# SCROD_CONN_A2.net
KiCad netlist of a schematic drawn in Altium Designer
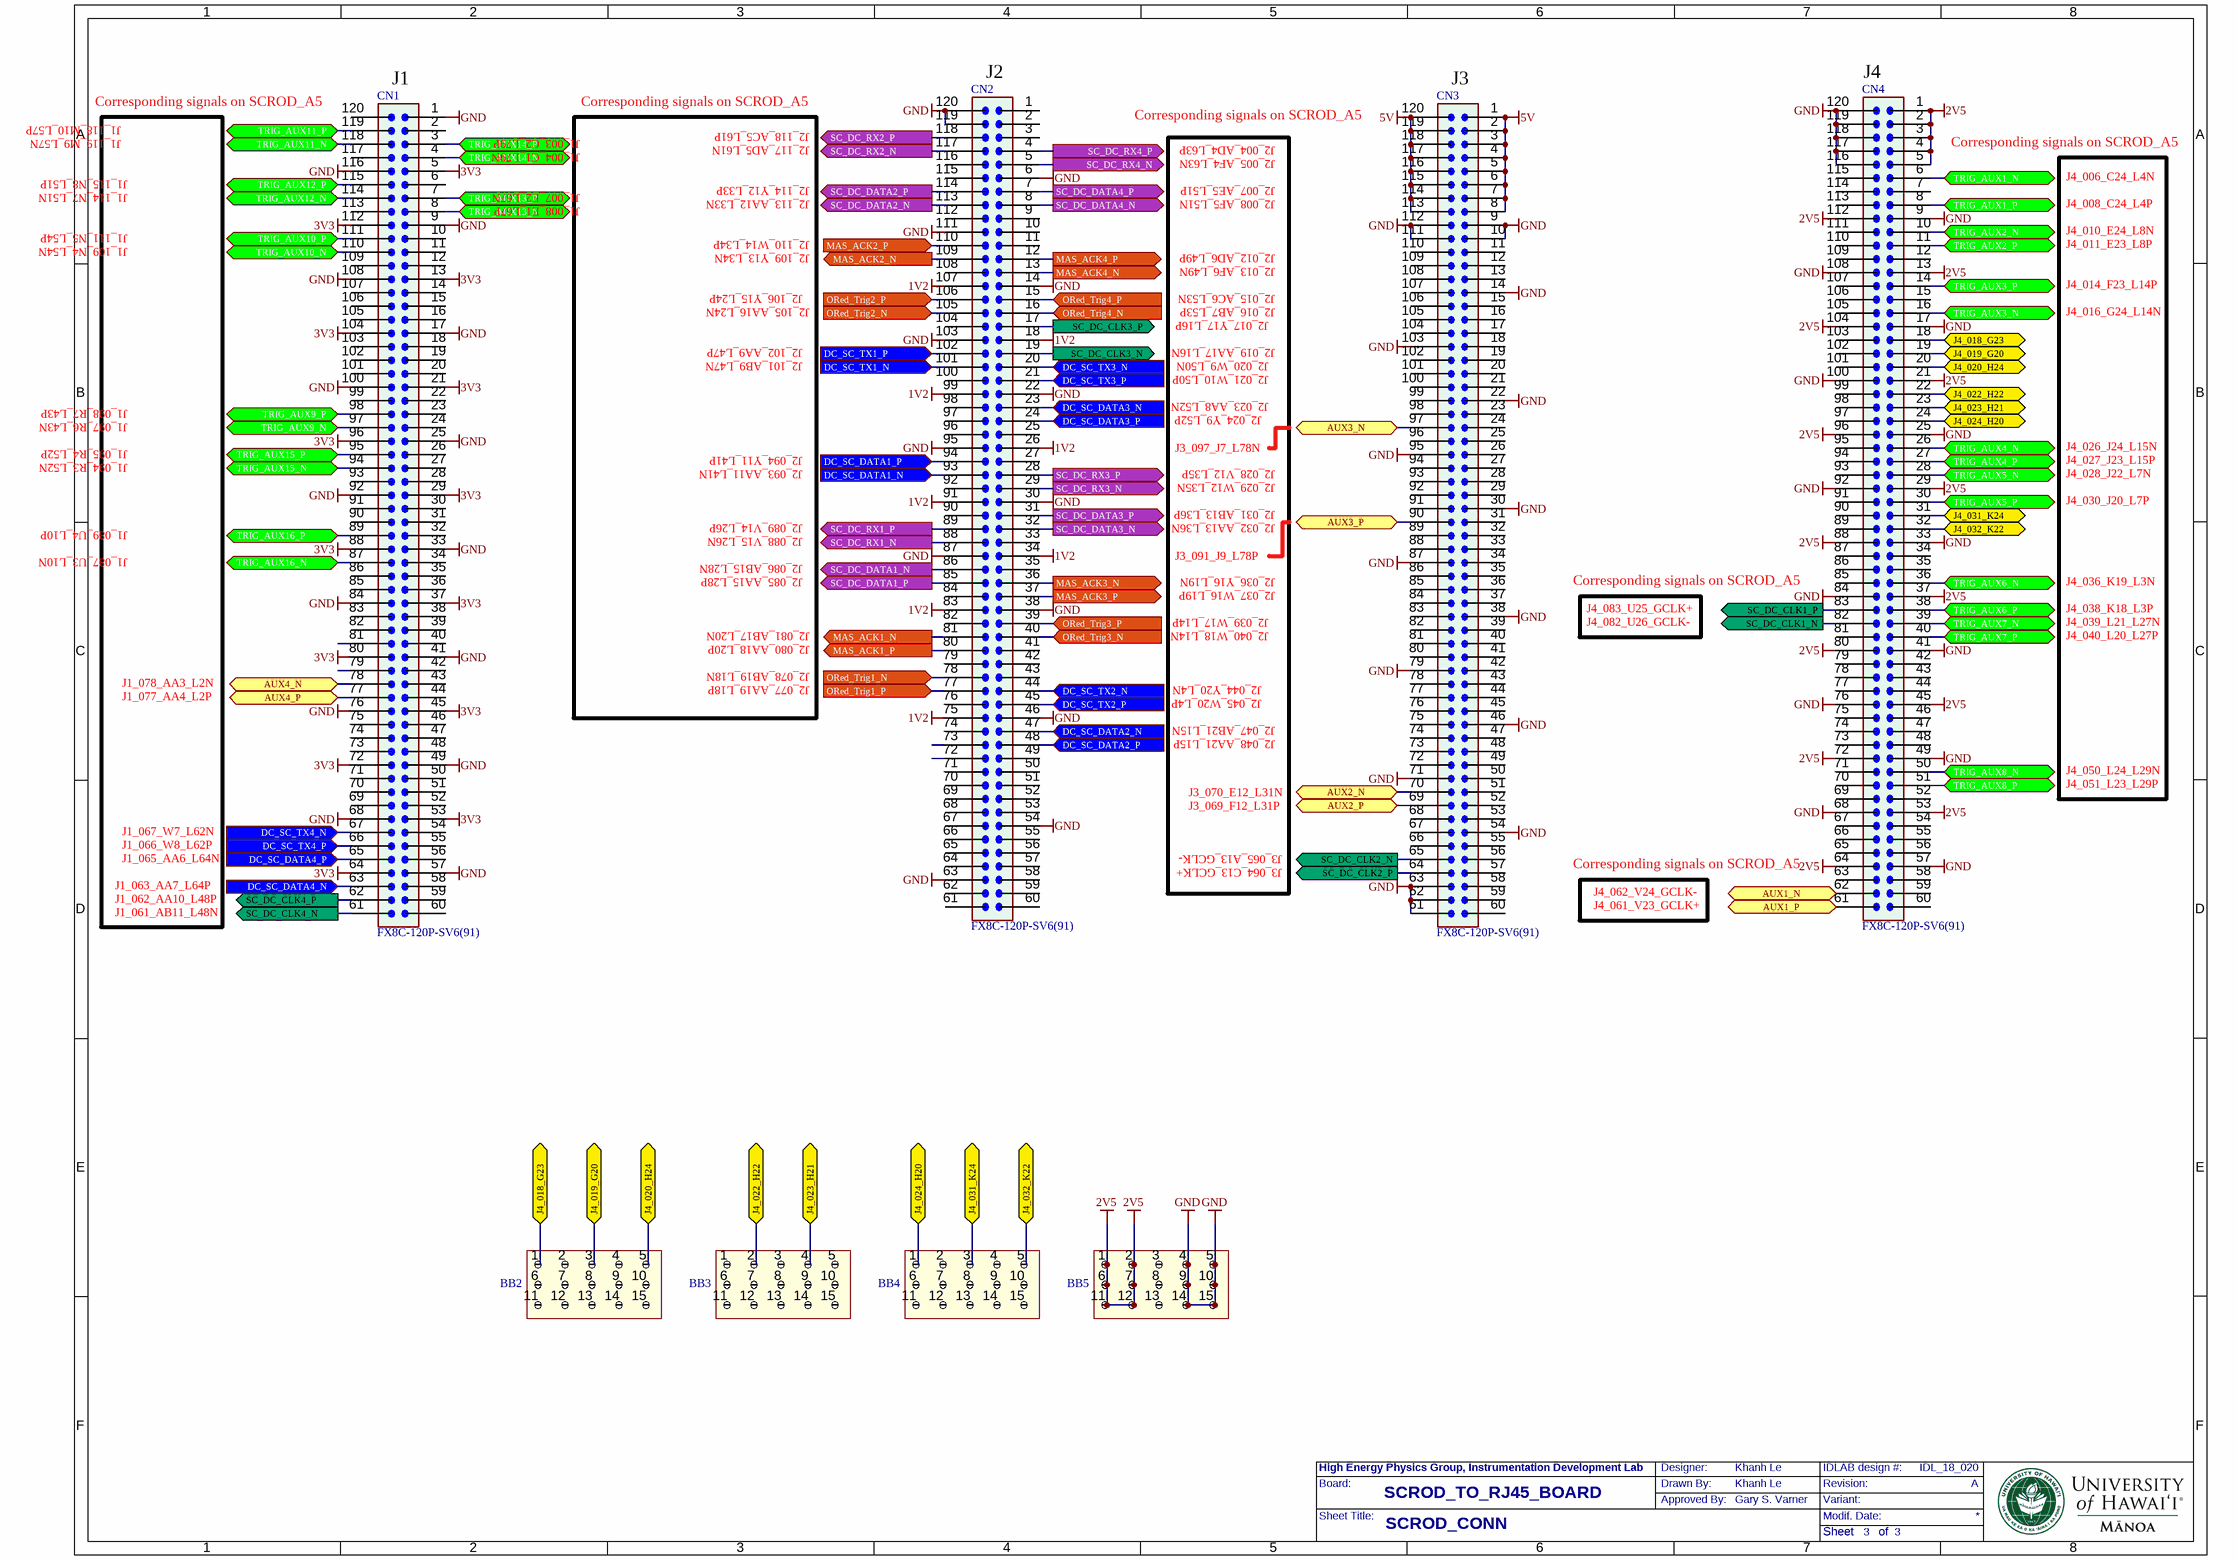
[diagram p0: SCROD_CONN_A2.SchDoc]

(export (version "E")
  (design (tool "Eeschema 10.0.6"))
  (components
    (comp (ref "BB2")
      (value "~")
      (footprint "Breadboard_3x5_100mil_pitch")
      (description "3X5 100mil pitch Breadboard")
      (libsource (lib "BMD") (part "3X5 Breadboard"))
    )
    (comp (ref "BB3")
      (value "~")
      (footprint "Breadboard_3x5_100mil_pitch")
      (description "3X5 100mil pitch Breadboard")
      (libsource (lib "BMD") (part "3X5 Breadboard"))
    )
    (comp (ref "BB4")
      (value "~")
      (footprint "Breadboard_3x5_100mil_pitch")
      (description "3X5 100mil pitch Breadboard")
      (libsource (lib "BMD") (part "3X5 Breadboard"))
    )
    (comp (ref "BB5")
      (value "~")
      (footprint "Breadboard_3x5_100mil_pitch")
      (description "3X5 100mil pitch Breadboard")
      (libsource (lib "BMD") (part "3X5 Breadboard"))
    )
    (comp (ref "CN1")
      (value "FX8C-120P-SV6(91)")
      (footprint "FX8C-120P-SV6(91)")
      (description "Hirose Connector 120pin SMD R0.6mm male")
      (fields (field (name "MANUFACTURER") "Hirose"))
      (libsource (lib "IDlab") (part "CN_FX8C-120P-SV6(91)"))
    )
    (comp (ref "CN2")
      (value "FX8C-120P-SV6(91)")
      (footprint "FX8C-120P-SV6(91)")
      (description "Hirose Connector 120pin SMD R0.6mm male")
      (fields (field (name "MANUFACTURER") "Hirose"))
      (libsource (lib "IDlab") (part "CN_FX8C-120P-SV6(91)"))
    )
    (comp (ref "CN3")
      (value "FX8C-120P-SV6(91)")
      (footprint "FX8C-120P-SV6(91)")
      (description "Hirose Connector 120pin SMD R0.6mm male")
      (fields (field (name "MANUFACTURER") "Hirose"))
      (libsource (lib "IDlab") (part "CN_FX8C-120P-SV6(91)"))
    )
    (comp (ref "CN4")
      (value "FX8C-120P-SV6(91)")
      (footprint "FX8C-120P-SV6(91)")
      (description "Hirose Connector 120pin SMD R0.6mm male")
      (fields (field (name "MANUFACTURER") "Hirose"))
      (libsource (lib "IDlab") (part "CN_FX8C-120P-SV6(91)"))
    )
  )
  (nets
    (net (code "1") (name "/AUX1_N") (class "Default") (node (ref "CN4") (pin "62") (pintype "passive")))
    (net (code "2") (name "/AUX1_P") (class "Default") (node (ref "CN4") (pin "61") (pintype "passive")))
    (net (code "3") (name "/AUX2_N") (class "Default") (node (ref "CN3") (pin "70") (pintype "passive")))
    (net (code "4") (name "/AUX2_P") (class "Default") (node (ref "CN3") (pin "69") (pintype "passive")))
    (net (code "5") (name "/AUX3_N") (class "Default") (node (ref "CN3") (pin "97") (pintype "passive")))
    (net (code "6") (name "/AUX3_P") (class "Default") (node (ref "CN3") (pin "90") (pintype "passive")))
    (net (code "7") (name "/AUX4_N") (class "Default") (node (ref "CN1") (pin "78") (pintype "passive")))
    (net (code "8") (name "/AUX4_P") (class "Default") (node (ref "CN1") (pin "77") (pintype "passive")))
    (net (code "9") (name "/DC_SC_DATA1_N") (class "Default")
      (node (ref "CN2") (pin "93") (pintype "passive"))
    )
    (net (code "10") (name "/DC_SC_DATA1_P") (class "Default")
      (node (ref "CN2") (pin "94") (pintype "passive"))
    )
    (net (code "11") (name "/DC_SC_DATA2_N") (class "Default")
      (node (ref "CN2") (pin "47") (pintype "passive"))
    )
    (net (code "12") (name "/DC_SC_DATA2_P") (class "Default")
      (node (ref "CN2") (pin "48") (pintype "passive"))
    )
    (net (code "13") (name "/DC_SC_DATA3_N") (class "Default")
      (node (ref "CN2") (pin "23") (pintype "passive"))
    )
    (net (code "14") (name "/DC_SC_DATA3_P") (class "Default")
      (node (ref "CN2") (pin "24") (pintype "passive"))
    )
    (net (code "15") (name "/DC_SC_DATA4_N") (class "Default")
      (node (ref "CN1") (pin "63") (pintype "passive"))
    )
    (net (code "16") (name "/DC_SC_DATA4_P") (class "Default")
      (node (ref "CN1") (pin "65") (pintype "passive"))
    )
    (net (code "17") (name "/DC_SC_TX1_N") (class "Default")
      (node (ref "CN2") (pin "101") (pintype "passive"))
    )
    (net (code "18") (name "/DC_SC_TX1_P") (class "Default")
      (node (ref "CN2") (pin "102") (pintype "passive"))
    )
    (net (code "19") (name "/DC_SC_TX2_N") (class "Default")
      (node (ref "CN2") (pin "44") (pintype "passive"))
    )
    (net (code "20") (name "/DC_SC_TX2_P") (class "Default")
      (node (ref "CN2") (pin "45") (pintype "passive"))
    )
    (net (code "21") (name "/DC_SC_TX3_N") (class "Default")
      (node (ref "CN2") (pin "20") (pintype "passive"))
    )
    (net (code "22") (name "/DC_SC_TX3_P") (class "Default")
      (node (ref "CN2") (pin "21") (pintype "passive"))
    )
    (net (code "23") (name "/DC_SC_TX4_N") (class "Default")
      (node (ref "CN1") (pin "67") (pintype "passive"))
    )
    (net (code "24") (name "/DC_SC_TX4_P") (class "Default")
      (node (ref "CN1") (pin "66") (pintype "passive"))
    )
    (net (code "25") (name "/J4_018_G23") (class "Default")
      (node (ref "BB2") (pin "1") (pinfunction "1_1") (pintype "passive"))
      (node (ref "CN4") (pin "18") (pintype "passive"))
    )
    (net (code "26") (name "/J4_019_G20") (class "Default")
      (node (ref "BB2") (pin "3") (pinfunction "3_3") (pintype "passive"))
      (node (ref "CN4") (pin "19") (pintype "passive"))
    )
    (net (code "27") (name "/J4_020_H24") (class "Default")
      (node (ref "BB2") (pin "5") (pinfunction "5_5") (pintype "passive"))
      (node (ref "CN4") (pin "20") (pintype "passive"))
    )
    (net (code "28") (name "/J4_022_H22") (class "Default")
      (node (ref "BB3") (pin "2") (pinfunction "2_2") (pintype "passive"))
      (node (ref "CN4") (pin "22") (pintype "passive"))
    )
    (net (code "29") (name "/J4_023_H21") (class "Default")
      (node (ref "BB3") (pin "4") (pinfunction "4_4") (pintype "passive"))
      (node (ref "CN4") (pin "23") (pintype "passive"))
    )
    (net (code "30") (name "/J4_024_H20") (class "Default")
      (node (ref "BB4") (pin "1") (pinfunction "1_1") (pintype "passive"))
      (node (ref "CN4") (pin "24") (pintype "passive"))
    )
    (net (code "31") (name "/J4_031_K24") (class "Default")
      (node (ref "BB4") (pin "3") (pinfunction "3_3") (pintype "passive"))
      (node (ref "CN4") (pin "31") (pintype "passive"))
    )
    (net (code "32") (name "/J4_032_K22") (class "Default")
      (node (ref "BB4") (pin "5") (pinfunction "5_5") (pintype "passive"))
      (node (ref "CN4") (pin "32") (pintype "passive"))
    )
    (net (code "33") (name "/MAS_ACK1_N") (class "Default") (node (ref "CN2") (pin "81") (pintype "passive")))
    (net (code "34") (name "/MAS_ACK1_P") (class "Default") (node (ref "CN2") (pin "80") (pintype "passive")))
    (net (code "35") (name "/MAS_ACK2_N") (class "Default")
      (node (ref "CN2") (pin "109") (pintype "passive"))
    )
    (net (code "36") (name "/MAS_ACK2_P") (class "Default")
      (node (ref "CN2") (pin "110") (pintype "passive"))
    )
    (net (code "37") (name "/MAS_ACK3_N") (class "Default") (node (ref "CN2") (pin "36") (pintype "passive")))
    (net (code "38") (name "/MAS_ACK3_P") (class "Default") (node (ref "CN2") (pin "37") (pintype "passive")))
    (net (code "39") (name "/MAS_ACK4_N") (class "Default") (node (ref "CN2") (pin "13") (pintype "passive")))
    (net (code "40") (name "/MAS_ACK4_P") (class "Default") (node (ref "CN2") (pin "12") (pintype "passive")))
    (net (code "41") (name "/ORed_Trig1_N") (class "Default")
      (node (ref "CN2") (pin "78") (pintype "passive"))
    )
    (net (code "42") (name "/ORed_Trig1_P") (class "Default")
      (node (ref "CN2") (pin "77") (pintype "passive"))
    )
    (net (code "43") (name "/ORed_Trig2_N") (class "Default")
      (node (ref "CN2") (pin "105") (pintype "passive"))
    )
    (net (code "44") (name "/ORed_Trig2_P") (class "Default")
      (node (ref "CN2") (pin "106") (pintype "passive"))
    )
    (net (code "45") (name "/ORed_Trig3_N") (class "Default")
      (node (ref "CN2") (pin "40") (pintype "passive"))
    )
    (net (code "46") (name "/ORed_Trig3_P") (class "Default")
      (node (ref "CN2") (pin "39") (pintype "passive"))
    )
    (net (code "47") (name "/ORed_Trig4_N") (class "Default")
      (node (ref "CN2") (pin "16") (pintype "passive"))
    )
    (net (code "48") (name "/ORed_Trig4_P") (class "Default")
      (node (ref "CN2") (pin "15") (pintype "passive"))
    )
    (net (code "49") (name "/SC_DC_CLK1_N") (class "Default")
      (node (ref "CN4") (pin "82") (pintype "passive"))
    )
    (net (code "50") (name "/SC_DC_CLK1_P") (class "Default")
      (node (ref "CN4") (pin "83") (pintype "passive"))
    )
    (net (code "51") (name "/SC_DC_CLK2_N") (class "Default")
      (node (ref "CN3") (pin "65") (pintype "passive"))
    )
    (net (code "52") (name "/SC_DC_CLK2_P") (class "Default")
      (node (ref "CN3") (pin "64") (pintype "passive"))
    )
    (net (code "53") (name "/SC_DC_CLK3_N") (class "Default")
      (node (ref "CN2") (pin "19") (pintype "passive"))
    )
    (net (code "54") (name "/SC_DC_CLK3_P") (class "Default")
      (node (ref "CN2") (pin "17") (pintype "passive"))
    )
    (net (code "55") (name "/SC_DC_CLK4_N") (class "Default")
      (node (ref "CN1") (pin "61") (pintype "passive"))
    )
    (net (code "56") (name "/SC_DC_CLK4_P") (class "Default")
      (node (ref "CN1") (pin "62") (pintype "passive"))
    )
    (net (code "57") (name "/SC_DC_DATA1_N") (class "Default")
      (node (ref "CN2") (pin "86") (pintype "passive"))
    )
    (net (code "58") (name "/SC_DC_DATA1_P") (class "Default")
      (node (ref "CN2") (pin "85") (pintype "passive"))
    )
    (net (code "59") (name "/SC_DC_DATA2_N") (class "Default")
      (node (ref "CN2") (pin "113") (pintype "passive"))
    )
    (net (code "60") (name "/SC_DC_DATA2_P") (class "Default")
      (node (ref "CN2") (pin "114") (pintype "passive"))
    )
    (net (code "61") (name "/SC_DC_DATA3_N") (class "Default")
      (node (ref "CN2") (pin "32") (pintype "passive"))
    )
    (net (code "62") (name "/SC_DC_DATA3_P") (class "Default")
      (node (ref "CN2") (pin "31") (pintype "passive"))
    )
    (net (code "63") (name "/SC_DC_DATA4_N") (class "Default")
      (node (ref "CN2") (pin "8") (pintype "passive"))
    )
    (net (code "64") (name "/SC_DC_DATA4_P") (class "Default")
      (node (ref "CN2") (pin "7") (pintype "passive"))
    )
    (net (code "65") (name "/SC_DC_RX1_N") (class "Default")
      (node (ref "CN2") (pin "88") (pintype "passive"))
    )
    (net (code "66") (name "/SC_DC_RX1_P") (class "Default")
      (node (ref "CN2") (pin "89") (pintype "passive"))
    )
    (net (code "67") (name "/SC_DC_RX2_N") (class "Default")
      (node (ref "CN2") (pin "117") (pintype "passive"))
    )
    (net (code "68") (name "/SC_DC_RX2_P") (class "Default")
      (node (ref "CN2") (pin "118") (pintype "passive"))
    )
    (net (code "69") (name "/SC_DC_RX3_N") (class "Default")
      (node (ref "CN2") (pin "29") (pintype "passive"))
    )
    (net (code "70") (name "/SC_DC_RX3_P") (class "Default")
      (node (ref "CN2") (pin "28") (pintype "passive"))
    )
    (net (code "71") (name "/SC_DC_RX4_N") (class "Default") (node (ref "CN2") (pin "5") (pintype "passive")))
    (net (code "72") (name "/SC_DC_RX4_P") (class "Default") (node (ref "CN2") (pin "4") (pintype "passive")))
    (net (code "73") (name "/TRIG_AUX1_N") (class "Default") (node (ref "CN4") (pin "6") (pintype "passive")))
    (net (code "74") (name "/TRIG_AUX1_P") (class "Default") (node (ref "CN4") (pin "8") (pintype "passive")))
    (net (code "75") (name "/TRIG_AUX2_N") (class "Default")
      (node (ref "CN4") (pin "10") (pintype "passive"))
    )
    (net (code "76") (name "/TRIG_AUX2_P") (class "Default")
      (node (ref "CN4") (pin "11") (pintype "passive"))
    )
    (net (code "77") (name "/TRIG_AUX3_N") (class "Default")
      (node (ref "CN4") (pin "16") (pintype "passive"))
    )
    (net (code "78") (name "/TRIG_AUX3_P") (class "Default")
      (node (ref "CN4") (pin "14") (pintype "passive"))
    )
    (net (code "79") (name "/TRIG_AUX4_N") (class "Default")
      (node (ref "CN4") (pin "26") (pintype "passive"))
    )
    (net (code "80") (name "/TRIG_AUX4_P") (class "Default")
      (node (ref "CN4") (pin "27") (pintype "passive"))
    )
    (net (code "81") (name "/TRIG_AUX5_N") (class "Default")
      (node (ref "CN4") (pin "28") (pintype "passive"))
    )
    (net (code "82") (name "/TRIG_AUX5_P") (class "Default")
      (node (ref "CN4") (pin "30") (pintype "passive"))
    )
    (net (code "83") (name "/TRIG_AUX6_N") (class "Default")
      (node (ref "CN4") (pin "36") (pintype "passive"))
    )
    (net (code "84") (name "/TRIG_AUX6_P") (class "Default")
      (node (ref "CN4") (pin "38") (pintype "passive"))
    )
    (net (code "85") (name "/TRIG_AUX7_N") (class "Default")
      (node (ref "CN4") (pin "39") (pintype "passive"))
    )
    (net (code "86") (name "/TRIG_AUX7_P") (class "Default")
      (node (ref "CN4") (pin "40") (pintype "passive"))
    )
    (net (code "87") (name "/TRIG_AUX8_N") (class "Default")
      (node (ref "CN4") (pin "50") (pintype "passive"))
    )
    (net (code "88") (name "/TRIG_AUX8_P") (class "Default")
      (node (ref "CN4") (pin "51") (pintype "passive"))
    )
    (net (code "89") (name "/TRIG_AUX9_N") (class "Default")
      (node (ref "CN1") (pin "97") (pintype "passive"))
    )
    (net (code "90") (name "/TRIG_AUX9_P") (class "Default")
      (node (ref "CN1") (pin "98") (pintype "passive"))
    )
    (net (code "91") (name "/TRIG_AUX10_N") (class "Default")
      (node (ref "CN1") (pin "110") (pintype "passive"))
    )
    (net (code "92") (name "/TRIG_AUX10_P") (class "Default")
      (node (ref "CN1") (pin "111") (pintype "passive"))
    )
    (net (code "93") (name "/TRIG_AUX11_N") (class "Default")
      (node (ref "CN1") (pin "118") (pintype "passive"))
    )
    (net (code "94") (name "/TRIG_AUX11_P") (class "Default")
      (node (ref "CN1") (pin "119") (pintype "passive"))
    )
    (net (code "95") (name "/TRIG_AUX12_N") (class "Default")
      (node (ref "CN1") (pin "114") (pintype "passive"))
    )
    (net (code "96") (name "/TRIG_AUX12_P") (class "Default")
      (node (ref "CN1") (pin "115") (pintype "passive"))
    )
    (net (code "97") (name "/TRIG_AUX13_N") (class "Default")
      (node (ref "CN1") (pin "8") (pintype "passive"))
    )
    (net (code "98") (name "/TRIG_AUX13_P") (class "Default")
      (node (ref "CN1") (pin "7") (pintype "passive"))
    )
    (net (code "99") (name "/TRIG_AUX14_N") (class "Default")
      (node (ref "CN1") (pin "4") (pintype "passive"))
    )
    (net (code "100") (name "/TRIG_AUX14_P") (class "Default")
      (node (ref "CN1") (pin "3") (pintype "passive"))
    )
    (net (code "101") (name "/TRIG_AUX15_N") (class "Default")
      (node (ref "CN1") (pin "94") (pintype "passive"))
    )
    (net (code "102") (name "/TRIG_AUX15_P") (class "Default")
      (node (ref "CN1") (pin "95") (pintype "passive"))
    )
    (net (code "103") (name "/TRIG_AUX16_N") (class "Default")
      (node (ref "CN1") (pin "87") (pintype "passive"))
    )
    (net (code "104") (name "/TRIG_AUX16_P") (class "Default")
      (node (ref "CN1") (pin "89") (pintype "passive"))
    )
    (net (code "105") (name "1V2") (class "Default")
      (node (ref "CN2") (pin "107") (pintype "passive"))
      (node (ref "CN2") (pin "18") (pintype "passive"))
      (node (ref "CN2") (pin "26") (pintype "passive"))
      (node (ref "CN2") (pin "34") (pintype "passive"))
      (node (ref "CN2") (pin "75") (pintype "passive"))
      (node (ref "CN2") (pin "83") (pintype "passive"))
      (node (ref "CN2") (pin "91") (pintype "passive"))
      (node (ref "CN2") (pin "99") (pintype "passive"))
    )
    (net (code "106") (name "2V5") (class "Default")
      (node (ref "BB5") (pin "1") (pinfunction "1_1") (pintype "passive"))
      (node (ref "BB5") (pin "11") (pinfunction "11_11") (pintype "passive"))
      (node (ref "BB5") (pin "12") (pinfunction "12_12") (pintype "passive"))
      (node (ref "BB5") (pin "2") (pinfunction "2_2") (pintype "passive"))
      (node (ref "BB5") (pin "6") (pinfunction "6_6") (pintype "passive"))
      (node (ref "BB5") (pin "7") (pinfunction "7_7") (pintype "passive"))
      (node (ref "CN4") (pin "1") (pintype "passive"))
      (node (ref "CN4") (pin "104") (pintype "passive"))
      (node (ref "CN4") (pin "112") (pintype "passive"))
      (node (ref "CN4") (pin "13") (pintype "passive"))
      (node (ref "CN4") (pin "2") (pintype "passive"))
      (node (ref "CN4") (pin "21") (pintype "passive"))
      (node (ref "CN4") (pin "29") (pintype "passive"))
      (node (ref "CN4") (pin "3") (pintype "passive"))
      (node (ref "CN4") (pin "37") (pintype "passive"))
      (node (ref "CN4") (pin "4") (pintype "passive"))
      (node (ref "CN4") (pin "45") (pintype "passive"))
      (node (ref "CN4") (pin "5") (pintype "passive"))
      (node (ref "CN4") (pin "53") (pintype "passive"))
      (node (ref "CN4") (pin "64") (pintype "passive"))
      (node (ref "CN4") (pin "72") (pintype "passive"))
      (node (ref "CN4") (pin "80") (pintype "passive"))
      (node (ref "CN4") (pin "88") (pintype "passive"))
      (node (ref "CN4") (pin "96") (pintype "passive"))
    )
    (net (code "107") (name "3V3") (class "Default")
      (node (ref "CN1") (pin "104") (pintype "passive"))
      (node (ref "CN1") (pin "112") (pintype "passive"))
      (node (ref "CN1") (pin "13") (pintype "passive"))
      (node (ref "CN1") (pin "21") (pintype "passive"))
      (node (ref "CN1") (pin "29") (pintype "passive"))
      (node (ref "CN1") (pin "37") (pintype "passive"))
      (node (ref "CN1") (pin "45") (pintype "passive"))
      (node (ref "CN1") (pin "5") (pintype "passive"))
      (node (ref "CN1") (pin "53") (pintype "passive"))
      (node (ref "CN1") (pin "64") (pintype "passive"))
      (node (ref "CN1") (pin "72") (pintype "passive"))
      (node (ref "CN1") (pin "80") (pintype "passive"))
      (node (ref "CN1") (pin "88") (pintype "passive"))
      (node (ref "CN1") (pin "96") (pintype "passive"))
    )
    (net (code "108") (name "5V") (class "Default")
      (node (ref "CN3") (pin "1") (pintype "passive"))
      (node (ref "CN3") (pin "113") (pintype "passive"))
      (node (ref "CN3") (pin "114") (pintype "passive"))
      (node (ref "CN3") (pin "115") (pintype "passive"))
      (node (ref "CN3") (pin "116") (pintype "passive"))
      (node (ref "CN3") (pin "117") (pintype "passive"))
      (node (ref "CN3") (pin "118") (pintype "passive"))
      (node (ref "CN3") (pin "119") (pintype "passive"))
      (node (ref "CN3") (pin "120") (pintype "passive"))
      (node (ref "CN3") (pin "2") (pintype "passive"))
      (node (ref "CN3") (pin "3") (pintype "passive"))
      (node (ref "CN3") (pin "4") (pintype "passive"))
      (node (ref "CN3") (pin "5") (pintype "passive"))
      (node (ref "CN3") (pin "6") (pintype "passive"))
      (node (ref "CN3") (pin "7") (pintype "passive"))
      (node (ref "CN3") (pin "8") (pintype "passive"))
    )
    (net (code "109") (name "GND") (class "Default")
      (node (ref "BB5") (pin "10") (pinfunction "10_10") (pintype "passive"))
      (node (ref "BB5") (pin "14") (pinfunction "14_14") (pintype "passive"))
      (node (ref "BB5") (pin "15") (pinfunction "15_15") (pintype "passive"))
      (node (ref "BB5") (pin "4") (pinfunction "4_4") (pintype "passive"))
      (node (ref "BB5") (pin "5") (pinfunction "5_5") (pintype "passive"))
      (node (ref "BB5") (pin "9") (pinfunction "9_9") (pintype "passive"))
      (node (ref "CN1") (pin "1") (pintype "passive"))
      (node (ref "CN1") (pin "100") (pintype "passive"))
      (node (ref "CN1") (pin "108") (pintype "passive"))
      (node (ref "CN1") (pin "116") (pintype "passive"))
      (node (ref "CN1") (pin "17") (pintype "passive"))
      (node (ref "CN1") (pin "25") (pintype "passive"))
      (node (ref "CN1") (pin "33") (pintype "passive"))
      (node (ref "CN1") (pin "41") (pintype "passive"))
      (node (ref "CN1") (pin "49") (pintype "passive"))
      (node (ref "CN1") (pin "57") (pintype "passive"))
      (node (ref "CN1") (pin "68") (pintype "passive"))
      (node (ref "CN1") (pin "76") (pintype "passive"))
      (node (ref "CN1") (pin "84") (pintype "passive"))
      (node (ref "CN1") (pin "9") (pintype "passive"))
      (node (ref "CN1") (pin "92") (pintype "passive"))
      (node (ref "CN2") (pin "103") (pintype "passive"))
      (node (ref "CN2") (pin "111") (pintype "passive"))
      (node (ref "CN2") (pin "119") (pintype "passive"))
      (node (ref "CN2") (pin "120") (pintype "passive"))
      (node (ref "CN2") (pin "14") (pintype "passive"))
      (node (ref "CN2") (pin "22") (pintype "passive"))
      (node (ref "CN2") (pin "30") (pintype "passive"))
      (node (ref "CN2") (pin "38") (pintype "passive"))
      (node (ref "CN2") (pin "46") (pintype "passive"))
      (node (ref "CN2") (pin "54") (pintype "passive"))
      (node (ref "CN2") (pin "6") (pintype "passive"))
      (node (ref "CN2") (pin "63") (pintype "passive"))
      (node (ref "CN2") (pin "87") (pintype "passive"))
      (node (ref "CN2") (pin "95") (pintype "passive"))
      (node (ref "CN3") (pin "10") (pintype "passive"))
      (node (ref "CN3") (pin "103") (pintype "passive"))
      (node (ref "CN3") (pin "111") (pintype "passive"))
      (node (ref "CN3") (pin "112") (pintype "passive"))
      (node (ref "CN3") (pin "14") (pintype "passive"))
      (node (ref "CN3") (pin "22") (pintype "passive"))
      (node (ref "CN3") (pin "30") (pintype "passive"))
      (node (ref "CN3") (pin "38") (pintype "passive"))
      (node (ref "CN3") (pin "46") (pintype "passive"))
      (node (ref "CN3") (pin "54") (pintype "passive"))
      (node (ref "CN3") (pin "61") (pintype "passive"))
      (node (ref "CN3") (pin "62") (pintype "passive"))
      (node (ref "CN3") (pin "63") (pintype "passive"))
      (node (ref "CN3") (pin "71") (pintype "passive"))
      (node (ref "CN3") (pin "79") (pintype "passive"))
      (node (ref "CN3") (pin "87") (pintype "passive"))
      (node (ref "CN3") (pin "9") (pintype "passive"))
      (node (ref "CN3") (pin "95") (pintype "passive"))
      (node (ref "CN4") (pin "100") (pintype "passive"))
      (node (ref "CN4") (pin "108") (pintype "passive"))
      (node (ref "CN4") (pin "116") (pintype "passive"))
      (node (ref "CN4") (pin "117") (pintype "passive"))
      (node (ref "CN4") (pin "118") (pintype "passive"))
      (node (ref "CN4") (pin "119") (pintype "passive"))
      (node (ref "CN4") (pin "120") (pintype "passive"))
      (node (ref "CN4") (pin "17") (pintype "passive"))
      (node (ref "CN4") (pin "25") (pintype "passive"))
      (node (ref "CN4") (pin "33") (pintype "passive"))
      (node (ref "CN4") (pin "41") (pintype "passive"))
      (node (ref "CN4") (pin "49") (pintype "passive"))
      (node (ref "CN4") (pin "57") (pintype "passive"))
      (node (ref "CN4") (pin "68") (pintype "passive"))
      (node (ref "CN4") (pin "76") (pintype "passive"))
      (node (ref "CN4") (pin "84") (pintype "passive"))
      (node (ref "CN4") (pin "9") (pintype "passive"))
      (node (ref "CN4") (pin "92") (pintype "passive"))
    )
    (net (code "110") (name "unconnected-(BB2-Pad2)") (class "Default")
      (node (ref "BB2") (pin "2") (pinfunction "2_2") (pintype "passive"))
    )
    (net (code "111") (name "unconnected-(BB2-Pad4)") (class "Default")
      (node (ref "BB2") (pin "4") (pinfunction "4_4") (pintype "passive"))
    )
    (net (code "112") (name "unconnected-(BB2-Pad6)") (class "Default")
      (node (ref "BB2") (pin "6") (pinfunction "6_6") (pintype "passive"))
    )
    (net (code "113") (name "unconnected-(BB2-Pad7)") (class "Default")
      (node (ref "BB2") (pin "7") (pinfunction "7_7") (pintype "passive"))
    )
    (net (code "114") (name "unconnected-(BB2-Pad8)") (class "Default")
      (node (ref "BB2") (pin "8") (pinfunction "8_8") (pintype "passive"))
    )
    (net (code "115") (name "unconnected-(BB2-Pad9)") (class "Default")
      (node (ref "BB2") (pin "9") (pinfunction "9_9") (pintype "passive"))
    )
    (net (code "116") (name "unconnected-(BB2-Pad10)") (class "Default")
      (node (ref "BB2") (pin "10") (pinfunction "10_10") (pintype "passive"))
    )
    (net (code "117") (name "unconnected-(BB2-Pad11)") (class "Default")
      (node (ref "BB2") (pin "11") (pinfunction "11_11") (pintype "passive"))
    )
    (net (code "118") (name "unconnected-(BB2-Pad12)") (class "Default")
      (node (ref "BB2") (pin "12") (pinfunction "12_12") (pintype "passive"))
    )
    (net (code "119") (name "unconnected-(BB2-Pad13)") (class "Default")
      (node (ref "BB2") (pin "13") (pinfunction "13_13") (pintype "passive"))
    )
    (net (code "120") (name "unconnected-(BB2-Pad14)") (class "Default")
      (node (ref "BB2") (pin "14") (pinfunction "14_14") (pintype "passive"))
    )
    (net (code "121") (name "unconnected-(BB2-Pad15)") (class "Default")
      (node (ref "BB2") (pin "15") (pinfunction "15_15") (pintype "passive"))
    )
    (net (code "122") (name "unconnected-(BB3-Pad1)") (class "Default")
      (node (ref "BB3") (pin "1") (pinfunction "1_1") (pintype "passive"))
    )
    (net (code "123") (name "unconnected-(BB3-Pad3)") (class "Default")
      (node (ref "BB3") (pin "3") (pinfunction "3_3") (pintype "passive"))
    )
    (net (code "124") (name "unconnected-(BB3-Pad5)") (class "Default")
      (node (ref "BB3") (pin "5") (pinfunction "5_5") (pintype "passive"))
    )
    (net (code "125") (name "unconnected-(BB3-Pad6)") (class "Default")
      (node (ref "BB3") (pin "6") (pinfunction "6_6") (pintype "passive"))
    )
    (net (code "126") (name "unconnected-(BB3-Pad7)") (class "Default")
      (node (ref "BB3") (pin "7") (pinfunction "7_7") (pintype "passive"))
    )
    (net (code "127") (name "unconnected-(BB3-Pad8)") (class "Default")
      (node (ref "BB3") (pin "8") (pinfunction "8_8") (pintype "passive"))
    )
    (net (code "128") (name "unconnected-(BB3-Pad9)") (class "Default")
      (node (ref "BB3") (pin "9") (pinfunction "9_9") (pintype "passive"))
    )
    (net (code "129") (name "unconnected-(BB3-Pad10)") (class "Default")
      (node (ref "BB3") (pin "10") (pinfunction "10_10") (pintype "passive"))
    )
    (net (code "130") (name "unconnected-(BB3-Pad11)") (class "Default")
      (node (ref "BB3") (pin "11") (pinfunction "11_11") (pintype "passive"))
    )
    (net (code "131") (name "unconnected-(BB3-Pad12)") (class "Default")
      (node (ref "BB3") (pin "12") (pinfunction "12_12") (pintype "passive"))
    )
    (net (code "132") (name "unconnected-(BB3-Pad13)") (class "Default")
      (node (ref "BB3") (pin "13") (pinfunction "13_13") (pintype "passive"))
    )
    (net (code "133") (name "unconnected-(BB3-Pad14)") (class "Default")
      (node (ref "BB3") (pin "14") (pinfunction "14_14") (pintype "passive"))
    )
    (net (code "134") (name "unconnected-(BB3-Pad15)") (class "Default")
      (node (ref "BB3") (pin "15") (pinfunction "15_15") (pintype "passive"))
    )
    (net (code "135") (name "unconnected-(BB4-Pad2)") (class "Default")
      (node (ref "BB4") (pin "2") (pinfunction "2_2") (pintype "passive"))
    )
    (net (code "136") (name "unconnected-(BB4-Pad4)") (class "Default")
      (node (ref "BB4") (pin "4") (pinfunction "4_4") (pintype "passive"))
    )
    (net (code "137") (name "unconnected-(BB4-Pad6)") (class "Default")
      (node (ref "BB4") (pin "6") (pinfunction "6_6") (pintype "passive"))
    )
    (net (code "138") (name "unconnected-(BB4-Pad7)") (class "Default")
      (node (ref "BB4") (pin "7") (pinfunction "7_7") (pintype "passive"))
    )
    (net (code "139") (name "unconnected-(BB4-Pad8)") (class "Default")
      (node (ref "BB4") (pin "8") (pinfunction "8_8") (pintype "passive"))
    )
    (net (code "140") (name "unconnected-(BB4-Pad9)") (class "Default")
      (node (ref "BB4") (pin "9") (pinfunction "9_9") (pintype "passive"))
    )
    (net (code "141") (name "unconnected-(BB4-Pad10)") (class "Default")
      (node (ref "BB4") (pin "10") (pinfunction "10_10") (pintype "passive"))
    )
    (net (code "142") (name "unconnected-(BB4-Pad11)") (class "Default")
      (node (ref "BB4") (pin "11") (pinfunction "11_11") (pintype "passive"))
    )
    (net (code "143") (name "unconnected-(BB4-Pad12)") (class "Default")
      (node (ref "BB4") (pin "12") (pinfunction "12_12") (pintype "passive"))
    )
    (net (code "144") (name "unconnected-(BB4-Pad13)") (class "Default")
      (node (ref "BB4") (pin "13") (pinfunction "13_13") (pintype "passive"))
    )
    (net (code "145") (name "unconnected-(BB4-Pad14)") (class "Default")
      (node (ref "BB4") (pin "14") (pinfunction "14_14") (pintype "passive"))
    )
    (net (code "146") (name "unconnected-(BB4-Pad15)") (class "Default")
      (node (ref "BB4") (pin "15") (pinfunction "15_15") (pintype "passive"))
    )
    (net (code "147") (name "unconnected-(BB5-Pad3)") (class "Default")
      (node (ref "BB5") (pin "3") (pinfunction "3_3") (pintype "passive"))
    )
    (net (code "148") (name "unconnected-(BB5-Pad8)") (class "Default")
      (node (ref "BB5") (pin "8") (pinfunction "8_8") (pintype "passive"))
    )
    (net (code "149") (name "unconnected-(BB5-Pad13)") (class "Default")
      (node (ref "BB5") (pin "13") (pinfunction "13_13") (pintype "passive"))
    )
    (net (code "150") (name "unconnected-(CN1-Pad2)") (class "Default")
      (node (ref "CN1") (pin "2") (pintype "passive"))
    )
    (net (code "151") (name "unconnected-(CN1-Pad6)") (class "Default")
      (node (ref "CN1") (pin "6") (pintype "passive"))
    )
    (net (code "152") (name "unconnected-(CN1-Pad10)") (class "Default")
      (node (ref "CN1") (pin "10") (pintype "passive"))
    )
    (net (code "153") (name "unconnected-(CN1-Pad11)") (class "Default")
      (node (ref "CN1") (pin "11") (pintype "passive"))
    )
    (net (code "154") (name "unconnected-(CN1-Pad12)") (class "Default")
      (node (ref "CN1") (pin "12") (pintype "passive"))
    )
    (net (code "155") (name "unconnected-(CN1-Pad14)") (class "Default")
      (node (ref "CN1") (pin "14") (pintype "passive"))
    )
    (net (code "156") (name "unconnected-(CN1-Pad15)") (class "Default")
      (node (ref "CN1") (pin "15") (pintype "passive"))
    )
    (net (code "157") (name "unconnected-(CN1-Pad16)") (class "Default")
      (node (ref "CN1") (pin "16") (pintype "passive"))
    )
    (net (code "158") (name "unconnected-(CN1-Pad18)") (class "Default")
      (node (ref "CN1") (pin "18") (pintype "passive"))
    )
    (net (code "159") (name "unconnected-(CN1-Pad19)") (class "Default")
      (node (ref "CN1") (pin "19") (pintype "passive"))
    )
    (net (code "160") (name "unconnected-(CN1-Pad20)") (class "Default")
      (node (ref "CN1") (pin "20") (pintype "passive"))
    )
    (net (code "161") (name "unconnected-(CN1-Pad22)") (class "Default")
      (node (ref "CN1") (pin "22") (pintype "passive"))
    )
    (net (code "162") (name "unconnected-(CN1-Pad23)") (class "Default")
      (node (ref "CN1") (pin "23") (pintype "passive"))
    )
    (net (code "163") (name "unconnected-(CN1-Pad24)") (class "Default")
      (node (ref "CN1") (pin "24") (pintype "passive"))
    )
    (net (code "164") (name "unconnected-(CN1-Pad26)") (class "Default")
      (node (ref "CN1") (pin "26") (pintype "passive"))
    )
    (net (code "165") (name "unconnected-(CN1-Pad27)") (class "Default")
      (node (ref "CN1") (pin "27") (pintype "passive"))
    )
    (net (code "166") (name "unconnected-(CN1-Pad28)") (class "Default")
      (node (ref "CN1") (pin "28") (pintype "passive"))
    )
    (net (code "167") (name "unconnected-(CN1-Pad30)") (class "Default")
      (node (ref "CN1") (pin "30") (pintype "passive"))
    )
    (net (code "168") (name "unconnected-(CN1-Pad31)") (class "Default")
      (node (ref "CN1") (pin "31") (pintype "passive"))
    )
    (net (code "169") (name "unconnected-(CN1-Pad32)") (class "Default")
      (node (ref "CN1") (pin "32") (pintype "passive"))
    )
    (net (code "170") (name "unconnected-(CN1-Pad34)") (class "Default")
      (node (ref "CN1") (pin "34") (pintype "passive"))
    )
    (net (code "171") (name "unconnected-(CN1-Pad35)") (class "Default")
      (node (ref "CN1") (pin "35") (pintype "passive"))
    )
    (net (code "172") (name "unconnected-(CN1-Pad36)") (class "Default")
      (node (ref "CN1") (pin "36") (pintype "passive"))
    )
    (net (code "173") (name "unconnected-(CN1-Pad38)") (class "Default")
      (node (ref "CN1") (pin "38") (pintype "passive"))
    )
    (net (code "174") (name "unconnected-(CN1-Pad39)") (class "Default")
      (node (ref "CN1") (pin "39") (pintype "passive"))
    )
    (net (code "175") (name "unconnected-(CN1-Pad40)") (class "Default")
      (node (ref "CN1") (pin "40") (pintype "passive"))
    )
    (net (code "176") (name "unconnected-(CN1-Pad42)") (class "Default")
      (node (ref "CN1") (pin "42") (pintype "passive"))
    )
    (net (code "177") (name "unconnected-(CN1-Pad43)") (class "Default")
      (node (ref "CN1") (pin "43") (pintype "passive"))
    )
    (net (code "178") (name "unconnected-(CN1-Pad44)") (class "Default")
      (node (ref "CN1") (pin "44") (pintype "passive"))
    )
    (net (code "179") (name "unconnected-(CN1-Pad46)") (class "Default")
      (node (ref "CN1") (pin "46") (pintype "passive"))
    )
    (net (code "180") (name "unconnected-(CN1-Pad47)") (class "Default")
      (node (ref "CN1") (pin "47") (pintype "passive"))
    )
    (net (code "181") (name "unconnected-(CN1-Pad48)") (class "Default")
      (node (ref "CN1") (pin "48") (pintype "passive"))
    )
    (net (code "182") (name "unconnected-(CN1-Pad50)") (class "Default")
      (node (ref "CN1") (pin "50") (pintype "passive"))
    )
    (net (code "183") (name "unconnected-(CN1-Pad51)") (class "Default")
      (node (ref "CN1") (pin "51") (pintype "passive"))
    )
    (net (code "184") (name "unconnected-(CN1-Pad52)") (class "Default")
      (node (ref "CN1") (pin "52") (pintype "passive"))
    )
    (net (code "185") (name "unconnected-(CN1-Pad54)") (class "Default")
      (node (ref "CN1") (pin "54") (pintype "passive"))
    )
    (net (code "186") (name "unconnected-(CN1-Pad55)") (class "Default")
      (node (ref "CN1") (pin "55") (pintype "passive"))
    )
    (net (code "187") (name "unconnected-(CN1-Pad56)") (class "Default")
      (node (ref "CN1") (pin "56") (pintype "passive"))
    )
    (net (code "188") (name "unconnected-(CN1-Pad58)") (class "Default")
      (node (ref "CN1") (pin "58") (pintype "passive"))
    )
    (net (code "189") (name "unconnected-(CN1-Pad59)") (class "Default")
      (node (ref "CN1") (pin "59") (pintype "passive"))
    )
    (net (code "190") (name "unconnected-(CN1-Pad60)") (class "Default")
      (node (ref "CN1") (pin "60") (pintype "passive"))
    )
    (net (code "191") (name "unconnected-(CN1-Pad69)") (class "Default")
      (node (ref "CN1") (pin "69") (pintype "passive"))
    )
    (net (code "192") (name "unconnected-(CN1-Pad70)") (class "Default")
      (node (ref "CN1") (pin "70") (pintype "passive"))
    )
    (net (code "193") (name "unconnected-(CN1-Pad71)") (class "Default")
      (node (ref "CN1") (pin "71") (pintype "passive"))
    )
    (net (code "194") (name "unconnected-(CN1-Pad73)") (class "Default")
      (node (ref "CN1") (pin "73") (pintype "passive"))
    )
    (net (code "195") (name "unconnected-(CN1-Pad74)") (class "Default")
      (node (ref "CN1") (pin "74") (pintype "passive"))
    )
    (net (code "196") (name "unconnected-(CN1-Pad75)") (class "Default")
      (node (ref "CN1") (pin "75") (pintype "passive"))
    )
    (net (code "197") (name "unconnected-(CN1-Pad79)") (class "Default")
      (node (ref "CN1") (pin "79") (pintype "passive"))
    )
    (net (code "198") (name "unconnected-(CN1-Pad81)") (class "Default")
      (node (ref "CN1") (pin "81") (pintype "passive"))
    )
    (net (code "199") (name "unconnected-(CN1-Pad82)") (class "Default")
      (node (ref "CN1") (pin "82") (pintype "passive"))
    )
    (net (code "200") (name "unconnected-(CN1-Pad83)") (class "Default")
      (node (ref "CN1") (pin "83") (pintype "passive"))
    )
    (net (code "201") (name "unconnected-(CN1-Pad85)") (class "Default")
      (node (ref "CN1") (pin "85") (pintype "passive"))
    )
    (net (code "202") (name "unconnected-(CN1-Pad86)") (class "Default")
      (node (ref "CN1") (pin "86") (pintype "passive"))
    )
    (net (code "203") (name "unconnected-(CN1-Pad90)") (class "Default")
      (node (ref "CN1") (pin "90") (pintype "passive"))
    )
    (net (code "204") (name "unconnected-(CN1-Pad91)") (class "Default")
      (node (ref "CN1") (pin "91") (pintype "passive"))
    )
    (net (code "205") (name "unconnected-(CN1-Pad93)") (class "Default")
      (node (ref "CN1") (pin "93") (pintype "passive"))
    )
    (net (code "206") (name "unconnected-(CN1-Pad99)") (class "Default")
      (node (ref "CN1") (pin "99") (pintype "passive"))
    )
    (net (code "207") (name "unconnected-(CN1-Pad101)") (class "Default")
      (node (ref "CN1") (pin "101") (pintype "passive"))
    )
    (net (code "208") (name "unconnected-(CN1-Pad102)") (class "Default")
      (node (ref "CN1") (pin "102") (pintype "passive"))
    )
    (net (code "209") (name "unconnected-(CN1-Pad103)") (class "Default")
      (node (ref "CN1") (pin "103") (pintype "passive"))
    )
    (net (code "210") (name "unconnected-(CN1-Pad105)") (class "Default")
      (node (ref "CN1") (pin "105") (pintype "passive"))
    )
    (net (code "211") (name "unconnected-(CN1-Pad106)") (class "Default")
      (node (ref "CN1") (pin "106") (pintype "passive"))
    )
    (net (code "212") (name "unconnected-(CN1-Pad107)") (class "Default")
      (node (ref "CN1") (pin "107") (pintype "passive"))
    )
    (net (code "213") (name "unconnected-(CN1-Pad109)") (class "Default")
      (node (ref "CN1") (pin "109") (pintype "passive"))
    )
    (net (code "214") (name "unconnected-(CN1-Pad113)") (class "Default")
      (node (ref "CN1") (pin "113") (pintype "passive"))
    )
    (net (code "215") (name "unconnected-(CN1-Pad117)") (class "Default")
      (node (ref "CN1") (pin "117") (pintype "passive"))
    )
    (net (code "216") (name "unconnected-(CN1-Pad120)") (class "Default")
      (node (ref "CN1") (pin "120") (pintype "passive"))
    )
    (net (code "217") (name "unconnected-(CN2-Pad1)") (class "Default")
      (node (ref "CN2") (pin "1") (pintype "passive"))
    )
    (net (code "218") (name "unconnected-(CN2-Pad2)") (class "Default")
      (node (ref "CN2") (pin "2") (pintype "passive"))
    )
    (net (code "219") (name "unconnected-(CN2-Pad3)") (class "Default")
      (node (ref "CN2") (pin "3") (pintype "passive"))
    )
    (net (code "220") (name "unconnected-(CN2-Pad9)") (class "Default")
      (node (ref "CN2") (pin "9") (pintype "passive"))
    )
    (net (code "221") (name "unconnected-(CN2-Pad10)") (class "Default")
      (node (ref "CN2") (pin "10") (pintype "passive"))
    )
    (net (code "222") (name "unconnected-(CN2-Pad11)") (class "Default")
      (node (ref "CN2") (pin "11") (pintype "passive"))
    )
    (net (code "223") (name "unconnected-(CN2-Pad25)") (class "Default")
      (node (ref "CN2") (pin "25") (pintype "passive"))
    )
    (net (code "224") (name "unconnected-(CN2-Pad27)") (class "Default")
      (node (ref "CN2") (pin "27") (pintype "passive"))
    )
    (net (code "225") (name "unconnected-(CN2-Pad33)") (class "Default")
      (node (ref "CN2") (pin "33") (pintype "passive"))
    )
    (net (code "226") (name "unconnected-(CN2-Pad35)") (class "Default")
      (node (ref "CN2") (pin "35") (pintype "passive"))
    )
    (net (code "227") (name "unconnected-(CN2-Pad41)") (class "Default")
      (node (ref "CN2") (pin "41") (pintype "passive"))
    )
    (net (code "228") (name "unconnected-(CN2-Pad42)") (class "Default")
      (node (ref "CN2") (pin "42") (pintype "passive"))
    )
    (net (code "229") (name "unconnected-(CN2-Pad43)") (class "Default")
      (node (ref "CN2") (pin "43") (pintype "passive"))
    )
    (net (code "230") (name "unconnected-(CN2-Pad49)") (class "Default")
      (node (ref "CN2") (pin "49") (pintype "passive"))
    )
    (net (code "231") (name "unconnected-(CN2-Pad50)") (class "Default")
      (node (ref "CN2") (pin "50") (pintype "passive"))
    )
    (net (code "232") (name "unconnected-(CN2-Pad51)") (class "Default")
      (node (ref "CN2") (pin "51") (pintype "passive"))
    )
    (net (code "233") (name "unconnected-(CN2-Pad52)") (class "Default")
      (node (ref "CN2") (pin "52") (pintype "passive"))
    )
    (net (code "234") (name "unconnected-(CN2-Pad53)") (class "Default")
      (node (ref "CN2") (pin "53") (pintype "passive"))
    )
    (net (code "235") (name "unconnected-(CN2-Pad55)") (class "Default")
      (node (ref "CN2") (pin "55") (pintype "passive"))
    )
    (net (code "236") (name "unconnected-(CN2-Pad56)") (class "Default")
      (node (ref "CN2") (pin "56") (pintype "passive"))
    )
    (net (code "237") (name "unconnected-(CN2-Pad57)") (class "Default")
      (node (ref "CN2") (pin "57") (pintype "passive"))
    )
    (net (code "238") (name "unconnected-(CN2-Pad58)") (class "Default")
      (node (ref "CN2") (pin "58") (pintype "passive"))
    )
    (net (code "239") (name "unconnected-(CN2-Pad59)") (class "Default")
      (node (ref "CN2") (pin "59") (pintype "passive"))
    )
    (net (code "240") (name "unconnected-(CN2-Pad60)") (class "Default")
      (node (ref "CN2") (pin "60") (pintype "passive"))
    )
    (net (code "241") (name "unconnected-(CN2-Pad61)") (class "Default")
      (node (ref "CN2") (pin "61") (pintype "passive"))
    )
    (net (code "242") (name "unconnected-(CN2-Pad62)") (class "Default")
      (node (ref "CN2") (pin "62") (pintype "passive"))
    )
    (net (code "243") (name "unconnected-(CN2-Pad64)") (class "Default")
      (node (ref "CN2") (pin "64") (pintype "passive"))
    )
    (net (code "244") (name "unconnected-(CN2-Pad65)") (class "Default")
      (node (ref "CN2") (pin "65") (pintype "passive"))
    )
    (net (code "245") (name "unconnected-(CN2-Pad66)") (class "Default")
      (node (ref "CN2") (pin "66") (pintype "passive"))
    )
    (net (code "246") (name "unconnected-(CN2-Pad67)") (class "Default")
      (node (ref "CN2") (pin "67") (pintype "passive"))
    )
    (net (code "247") (name "unconnected-(CN2-Pad68)") (class "Default")
      (node (ref "CN2") (pin "68") (pintype "passive"))
    )
    (net (code "248") (name "unconnected-(CN2-Pad69)") (class "Default")
      (node (ref "CN2") (pin "69") (pintype "passive"))
    )
    (net (code "249") (name "unconnected-(CN2-Pad70)") (class "Default")
      (node (ref "CN2") (pin "70") (pintype "passive"))
    )
    (net (code "250") (name "unconnected-(CN2-Pad71)") (class "Default")
      (node (ref "CN2") (pin "71") (pintype "passive"))
    )
    (net (code "251") (name "unconnected-(CN2-Pad72)") (class "Default")
      (node (ref "CN2") (pin "72") (pintype "passive"))
    )
    (net (code "252") (name "unconnected-(CN2-Pad73)") (class "Default")
      (node (ref "CN2") (pin "73") (pintype "passive"))
    )
    (net (code "253") (name "unconnected-(CN2-Pad74)") (class "Default")
      (node (ref "CN2") (pin "74") (pintype "passive"))
    )
    (net (code "254") (name "unconnected-(CN2-Pad76)") (class "Default")
      (node (ref "CN2") (pin "76") (pintype "passive"))
    )
    (net (code "255") (name "unconnected-(CN2-Pad79)") (class "Default")
      (node (ref "CN2") (pin "79") (pintype "passive"))
    )
    (net (code "256") (name "unconnected-(CN2-Pad82)") (class "Default")
      (node (ref "CN2") (pin "82") (pintype "passive"))
    )
    (net (code "257") (name "unconnected-(CN2-Pad84)") (class "Default")
      (node (ref "CN2") (pin "84") (pintype "passive"))
    )
    (net (code "258") (name "unconnected-(CN2-Pad90)") (class "Default")
      (node (ref "CN2") (pin "90") (pintype "passive"))
    )
    (net (code "259") (name "unconnected-(CN2-Pad92)") (class "Default")
      (node (ref "CN2") (pin "92") (pintype "passive"))
    )
    (net (code "260") (name "unconnected-(CN2-Pad96)") (class "Default")
      (node (ref "CN2") (pin "96") (pintype "passive"))
    )
    (net (code "261") (name "unconnected-(CN2-Pad97)") (class "Default")
      (node (ref "CN2") (pin "97") (pintype "passive"))
    )
    (net (code "262") (name "unconnected-(CN2-Pad98)") (class "Default")
      (node (ref "CN2") (pin "98") (pintype "passive"))
    )
    (net (code "263") (name "unconnected-(CN2-Pad100)") (class "Default")
      (node (ref "CN2") (pin "100") (pintype "passive"))
    )
    (net (code "264") (name "unconnected-(CN2-Pad104)") (class "Default")
      (node (ref "CN2") (pin "104") (pintype "passive"))
    )
    (net (code "265") (name "unconnected-(CN2-Pad108)") (class "Default")
      (node (ref "CN2") (pin "108") (pintype "passive"))
    )
    (net (code "266") (name "unconnected-(CN2-Pad112)") (class "Default")
      (node (ref "CN2") (pin "112") (pintype "passive"))
    )
    (net (code "267") (name "unconnected-(CN2-Pad115)") (class "Default")
      (node (ref "CN2") (pin "115") (pintype "passive"))
    )
    (net (code "268") (name "unconnected-(CN2-Pad116)") (class "Default")
      (node (ref "CN2") (pin "116") (pintype "passive"))
    )
    (net (code "269") (name "unconnected-(CN3-Pad11)") (class "Default")
      (node (ref "CN3") (pin "11") (pintype "passive"))
    )
    (net (code "270") (name "unconnected-(CN3-Pad12)") (class "Default")
      (node (ref "CN3") (pin "12") (pintype "passive"))
    )
    (net (code "271") (name "unconnected-(CN3-Pad13)") (class "Default")
      (node (ref "CN3") (pin "13") (pintype "passive"))
    )
    (net (code "272") (name "unconnected-(CN3-Pad15)") (class "Default")
      (node (ref "CN3") (pin "15") (pintype "passive"))
    )
    (net (code "273") (name "unconnected-(CN3-Pad16)") (class "Default")
      (node (ref "CN3") (pin "16") (pintype "passive"))
    )
    (net (code "274") (name "unconnected-(CN3-Pad17)") (class "Default")
      (node (ref "CN3") (pin "17") (pintype "passive"))
    )
    (net (code "275") (name "unconnected-(CN3-Pad18)") (class "Default")
      (node (ref "CN3") (pin "18") (pintype "passive"))
    )
    (net (code "276") (name "unconnected-(CN3-Pad19)") (class "Default")
      (node (ref "CN3") (pin "19") (pintype "passive"))
    )
    (net (code "277") (name "unconnected-(CN3-Pad20)") (class "Default")
      (node (ref "CN3") (pin "20") (pintype "passive"))
    )
    (net (code "278") (name "unconnected-(CN3-Pad21)") (class "Default")
      (node (ref "CN3") (pin "21") (pintype "passive"))
    )
    (net (code "279") (name "unconnected-(CN3-Pad23)") (class "Default")
      (node (ref "CN3") (pin "23") (pintype "passive"))
    )
    (net (code "280") (name "unconnected-(CN3-Pad24)") (class "Default")
      (node (ref "CN3") (pin "24") (pintype "passive"))
    )
    (net (code "281") (name "unconnected-(CN3-Pad25)") (class "Default")
      (node (ref "CN3") (pin "25") (pintype "passive"))
    )
    (net (code "282") (name "unconnected-(CN3-Pad26)") (class "Default")
      (node (ref "CN3") (pin "26") (pintype "passive"))
    )
    (net (code "283") (name "unconnected-(CN3-Pad27)") (class "Default")
      (node (ref "CN3") (pin "27") (pintype "passive"))
    )
    (net (code "284") (name "unconnected-(CN3-Pad28)") (class "Default")
      (node (ref "CN3") (pin "28") (pintype "passive"))
    )
    (net (code "285") (name "unconnected-(CN3-Pad29)") (class "Default")
      (node (ref "CN3") (pin "29") (pintype "passive"))
    )
    (net (code "286") (name "unconnected-(CN3-Pad31)") (class "Default")
      (node (ref "CN3") (pin "31") (pintype "passive"))
    )
    (net (code "287") (name "unconnected-(CN3-Pad32)") (class "Default")
      (node (ref "CN3") (pin "32") (pintype "passive"))
    )
    (net (code "288") (name "unconnected-(CN3-Pad33)") (class "Default")
      (node (ref "CN3") (pin "33") (pintype "passive"))
    )
    (net (code "289") (name "unconnected-(CN3-Pad34)") (class "Default")
      (node (ref "CN3") (pin "34") (pintype "passive"))
    )
    (net (code "290") (name "unconnected-(CN3-Pad35)") (class "Default")
      (node (ref "CN3") (pin "35") (pintype "passive"))
    )
    (net (code "291") (name "unconnected-(CN3-Pad36)") (class "Default")
      (node (ref "CN3") (pin "36") (pintype "passive"))
    )
    (net (code "292") (name "unconnected-(CN3-Pad37)") (class "Default")
      (node (ref "CN3") (pin "37") (pintype "passive"))
    )
    (net (code "293") (name "unconnected-(CN3-Pad39)") (class "Default")
      (node (ref "CN3") (pin "39") (pintype "passive"))
    )
    (net (code "294") (name "unconnected-(CN3-Pad40)") (class "Default")
      (node (ref "CN3") (pin "40") (pintype "passive"))
    )
    (net (code "295") (name "unconnected-(CN3-Pad41)") (class "Default")
      (node (ref "CN3") (pin "41") (pintype "passive"))
    )
    (net (code "296") (name "unconnected-(CN3-Pad42)") (class "Default")
      (node (ref "CN3") (pin "42") (pintype "passive"))
    )
    (net (code "297") (name "unconnected-(CN3-Pad43)") (class "Default")
      (node (ref "CN3") (pin "43") (pintype "passive"))
    )
    (net (code "298") (name "unconnected-(CN3-Pad44)") (class "Default")
      (node (ref "CN3") (pin "44") (pintype "passive"))
    )
    (net (code "299") (name "unconnected-(CN3-Pad45)") (class "Default")
      (node (ref "CN3") (pin "45") (pintype "passive"))
    )
    (net (code "300") (name "unconnected-(CN3-Pad47)") (class "Default")
      (node (ref "CN3") (pin "47") (pintype "passive"))
    )
    (net (code "301") (name "unconnected-(CN3-Pad48)") (class "Default")
      (node (ref "CN3") (pin "48") (pintype "passive"))
    )
    (net (code "302") (name "unconnected-(CN3-Pad49)") (class "Default")
      (node (ref "CN3") (pin "49") (pintype "passive"))
    )
    (net (code "303") (name "unconnected-(CN3-Pad50)") (class "Default")
      (node (ref "CN3") (pin "50") (pintype "passive"))
    )
    (net (code "304") (name "unconnected-(CN3-Pad51)") (class "Default")
      (node (ref "CN3") (pin "51") (pintype "passive"))
    )
    (net (code "305") (name "unconnected-(CN3-Pad52)") (class "Default")
      (node (ref "CN3") (pin "52") (pintype "passive"))
    )
    (net (code "306") (name "unconnected-(CN3-Pad53)") (class "Default")
      (node (ref "CN3") (pin "53") (pintype "passive"))
    )
    (net (code "307") (name "unconnected-(CN3-Pad55)") (class "Default")
      (node (ref "CN3") (pin "55") (pintype "passive"))
    )
    (net (code "308") (name "unconnected-(CN3-Pad56)") (class "Default")
      (node (ref "CN3") (pin "56") (pintype "passive"))
    )
    (net (code "309") (name "unconnected-(CN3-Pad57)") (class "Default")
      (node (ref "CN3") (pin "57") (pintype "passive"))
    )
    (net (code "310") (name "unconnected-(CN3-Pad58)") (class "Default")
      (node (ref "CN3") (pin "58") (pintype "passive"))
    )
    (net (code "311") (name "unconnected-(CN3-Pad59)") (class "Default")
      (node (ref "CN3") (pin "59") (pintype "passive"))
    )
    (net (code "312") (name "unconnected-(CN3-Pad60)") (class "Default")
      (node (ref "CN3") (pin "60") (pintype "passive"))
    )
    (net (code "313") (name "unconnected-(CN3-Pad66)") (class "Default")
      (node (ref "CN3") (pin "66") (pintype "passive"))
    )
    (net (code "314") (name "unconnected-(CN3-Pad67)") (class "Default")
      (node (ref "CN3") (pin "67") (pintype "passive"))
    )
    (net (code "315") (name "unconnected-(CN3-Pad68)") (class "Default")
      (node (ref "CN3") (pin "68") (pintype "passive"))
    )
    (net (code "316") (name "unconnected-(CN3-Pad72)") (class "Default")
      (node (ref "CN3") (pin "72") (pintype "passive"))
    )
    (net (code "317") (name "unconnected-(CN3-Pad73)") (class "Default")
      (node (ref "CN3") (pin "73") (pintype "passive"))
    )
    (net (code "318") (name "unconnected-(CN3-Pad74)") (class "Default")
      (node (ref "CN3") (pin "74") (pintype "passive"))
    )
    (net (code "319") (name "unconnected-(CN3-Pad75)") (class "Default")
      (node (ref "CN3") (pin "75") (pintype "passive"))
    )
    (net (code "320") (name "unconnected-(CN3-Pad76)") (class "Default")
      (node (ref "CN3") (pin "76") (pintype "passive"))
    )
    (net (code "321") (name "unconnected-(CN3-Pad77)") (class "Default")
      (node (ref "CN3") (pin "77") (pintype "passive"))
    )
    (net (code "322") (name "unconnected-(CN3-Pad78)") (class "Default")
      (node (ref "CN3") (pin "78") (pintype "passive"))
    )
    (net (code "323") (name "unconnected-(CN3-Pad80)") (class "Default")
      (node (ref "CN3") (pin "80") (pintype "passive"))
    )
    (net (code "324") (name "unconnected-(CN3-Pad81)") (class "Default")
      (node (ref "CN3") (pin "81") (pintype "passive"))
    )
    (net (code "325") (name "unconnected-(CN3-Pad82)") (class "Default")
      (node (ref "CN3") (pin "82") (pintype "passive"))
    )
    (net (code "326") (name "unconnected-(CN3-Pad83)") (class "Default")
      (node (ref "CN3") (pin "83") (pintype "passive"))
    )
    (net (code "327") (name "unconnected-(CN3-Pad84)") (class "Default")
      (node (ref "CN3") (pin "84") (pintype "passive"))
    )
    (net (code "328") (name "unconnected-(CN3-Pad85)") (class "Default")
      (node (ref "CN3") (pin "85") (pintype "passive"))
    )
    (net (code "329") (name "unconnected-(CN3-Pad86)") (class "Default")
      (node (ref "CN3") (pin "86") (pintype "passive"))
    )
    (net (code "330") (name "unconnected-(CN3-Pad88)") (class "Default")
      (node (ref "CN3") (pin "88") (pintype "passive"))
    )
    (net (code "331") (name "unconnected-(CN3-Pad89)") (class "Default")
      (node (ref "CN3") (pin "89") (pintype "passive"))
    )
    (net (code "332") (name "unconnected-(CN3-Pad91)") (class "Default")
      (node (ref "CN3") (pin "91") (pintype "passive"))
    )
    (net (code "333") (name "unconnected-(CN3-Pad92)") (class "Default")
      (node (ref "CN3") (pin "92") (pintype "passive"))
    )
    (net (code "334") (name "unconnected-(CN3-Pad93)") (class "Default")
      (node (ref "CN3") (pin "93") (pintype "passive"))
    )
    (net (code "335") (name "unconnected-(CN3-Pad94)") (class "Default")
      (node (ref "CN3") (pin "94") (pintype "passive"))
    )
    (net (code "336") (name "unconnected-(CN3-Pad96)") (class "Default")
      (node (ref "CN3") (pin "96") (pintype "passive"))
    )
    (net (code "337") (name "unconnected-(CN3-Pad98)") (class "Default")
      (node (ref "CN3") (pin "98") (pintype "passive"))
    )
    (net (code "338") (name "unconnected-(CN3-Pad99)") (class "Default")
      (node (ref "CN3") (pin "99") (pintype "passive"))
    )
    (net (code "339") (name "unconnected-(CN3-Pad100)") (class "Default")
      (node (ref "CN3") (pin "100") (pintype "passive"))
    )
    (net (code "340") (name "unconnected-(CN3-Pad101)") (class "Default")
      (node (ref "CN3") (pin "101") (pintype "passive"))
    )
    (net (code "341") (name "unconnected-(CN3-Pad102)") (class "Default")
      (node (ref "CN3") (pin "102") (pintype "passive"))
    )
    (net (code "342") (name "unconnected-(CN3-Pad104)") (class "Default")
      (node (ref "CN3") (pin "104") (pintype "passive"))
    )
    (net (code "343") (name "unconnected-(CN3-Pad105)") (class "Default")
      (node (ref "CN3") (pin "105") (pintype "passive"))
    )
    (net (code "344") (name "unconnected-(CN3-Pad106)") (class "Default")
      (node (ref "CN3") (pin "106") (pintype "passive"))
    )
    (net (code "345") (name "unconnected-(CN3-Pad107)") (class "Default")
      (node (ref "CN3") (pin "107") (pintype "passive"))
    )
    (net (code "346") (name "unconnected-(CN3-Pad108)") (class "Default")
      (node (ref "CN3") (pin "108") (pintype "passive"))
    )
    (net (code "347") (name "unconnected-(CN3-Pad109)") (class "Default")
      (node (ref "CN3") (pin "109") (pintype "passive"))
    )
    (net (code "348") (name "unconnected-(CN3-Pad110)") (class "Default")
      (node (ref "CN3") (pin "110") (pintype "passive"))
    )
    (net (code "349") (name "unconnected-(CN4-Pad7)") (class "Default")
      (node (ref "CN4") (pin "7") (pintype "passive"))
    )
    (net (code "350") (name "unconnected-(CN4-Pad12)") (class "Default")
      (node (ref "CN4") (pin "12") (pintype "passive"))
    )
    (net (code "351") (name "unconnected-(CN4-Pad15)") (class "Default")
      (node (ref "CN4") (pin "15") (pintype "passive"))
    )
    (net (code "352") (name "unconnected-(CN4-Pad34)") (class "Default")
      (node (ref "CN4") (pin "34") (pintype "passive"))
    )
    (net (code "353") (name "unconnected-(CN4-Pad35)") (class "Default")
      (node (ref "CN4") (pin "35") (pintype "passive"))
    )
    (net (code "354") (name "unconnected-(CN4-Pad42)") (class "Default")
      (node (ref "CN4") (pin "42") (pintype "passive"))
    )
    (net (code "355") (name "unconnected-(CN4-Pad43)") (class "Default")
      (node (ref "CN4") (pin "43") (pintype "passive"))
    )
    (net (code "356") (name "unconnected-(CN4-Pad44)") (class "Default")
      (node (ref "CN4") (pin "44") (pintype "passive"))
    )
    (net (code "357") (name "unconnected-(CN4-Pad46)") (class "Default")
      (node (ref "CN4") (pin "46") (pintype "passive"))
    )
    (net (code "358") (name "unconnected-(CN4-Pad47)") (class "Default")
      (node (ref "CN4") (pin "47") (pintype "passive"))
    )
    (net (code "359") (name "unconnected-(CN4-Pad48)") (class "Default")
      (node (ref "CN4") (pin "48") (pintype "passive"))
    )
    (net (code "360") (name "unconnected-(CN4-Pad52)") (class "Default")
      (node (ref "CN4") (pin "52") (pintype "passive"))
    )
    (net (code "361") (name "unconnected-(CN4-Pad54)") (class "Default")
      (node (ref "CN4") (pin "54") (pintype "passive"))
    )
    (net (code "362") (name "unconnected-(CN4-Pad55)") (class "Default")
      (node (ref "CN4") (pin "55") (pintype "passive"))
    )
    (net (code "363") (name "unconnected-(CN4-Pad56)") (class "Default")
      (node (ref "CN4") (pin "56") (pintype "passive"))
    )
    (net (code "364") (name "unconnected-(CN4-Pad58)") (class "Default")
      (node (ref "CN4") (pin "58") (pintype "passive"))
    )
    (net (code "365") (name "unconnected-(CN4-Pad59)") (class "Default")
      (node (ref "CN4") (pin "59") (pintype "passive"))
    )
    (net (code "366") (name "unconnected-(CN4-Pad60)") (class "Default")
      (node (ref "CN4") (pin "60") (pintype "passive"))
    )
    (net (code "367") (name "unconnected-(CN4-Pad63)") (class "Default")
      (node (ref "CN4") (pin "63") (pintype "passive"))
    )
    (net (code "368") (name "unconnected-(CN4-Pad65)") (class "Default")
      (node (ref "CN4") (pin "65") (pintype "passive"))
    )
    (net (code "369") (name "unconnected-(CN4-Pad66)") (class "Default")
      (node (ref "CN4") (pin "66") (pintype "passive"))
    )
    (net (code "370") (name "unconnected-(CN4-Pad67)") (class "Default")
      (node (ref "CN4") (pin "67") (pintype "passive"))
    )
    (net (code "371") (name "unconnected-(CN4-Pad69)") (class "Default")
      (node (ref "CN4") (pin "69") (pintype "passive"))
    )
    (net (code "372") (name "unconnected-(CN4-Pad70)") (class "Default")
      (node (ref "CN4") (pin "70") (pintype "passive"))
    )
    (net (code "373") (name "unconnected-(CN4-Pad71)") (class "Default")
      (node (ref "CN4") (pin "71") (pintype "passive"))
    )
    (net (code "374") (name "unconnected-(CN4-Pad73)") (class "Default")
      (node (ref "CN4") (pin "73") (pintype "passive"))
    )
    (net (code "375") (name "unconnected-(CN4-Pad74)") (class "Default")
      (node (ref "CN4") (pin "74") (pintype "passive"))
    )
    (net (code "376") (name "unconnected-(CN4-Pad75)") (class "Default")
      (node (ref "CN4") (pin "75") (pintype "passive"))
    )
    (net (code "377") (name "unconnected-(CN4-Pad77)") (class "Default")
      (node (ref "CN4") (pin "77") (pintype "passive"))
    )
    (net (code "378") (name "unconnected-(CN4-Pad78)") (class "Default")
      (node (ref "CN4") (pin "78") (pintype "passive"))
    )
    (net (code "379") (name "unconnected-(CN4-Pad79)") (class "Default")
      (node (ref "CN4") (pin "79") (pintype "passive"))
    )
    (net (code "380") (name "unconnected-(CN4-Pad81)") (class "Default")
      (node (ref "CN4") (pin "81") (pintype "passive"))
    )
    (net (code "381") (name "unconnected-(CN4-Pad85)") (class "Default")
      (node (ref "CN4") (pin "85") (pintype "passive"))
    )
    (net (code "382") (name "unconnected-(CN4-Pad86)") (class "Default")
      (node (ref "CN4") (pin "86") (pintype "passive"))
    )
    (net (code "383") (name "unconnected-(CN4-Pad87)") (class "Default")
      (node (ref "CN4") (pin "87") (pintype "passive"))
    )
    (net (code "384") (name "unconnected-(CN4-Pad89)") (class "Default")
      (node (ref "CN4") (pin "89") (pintype "passive"))
    )
    (net (code "385") (name "unconnected-(CN4-Pad90)") (class "Default")
      (node (ref "CN4") (pin "90") (pintype "passive"))
    )
    (net (code "386") (name "unconnected-(CN4-Pad91)") (class "Default")
      (node (ref "CN4") (pin "91") (pintype "passive"))
    )
    (net (code "387") (name "unconnected-(CN4-Pad93)") (class "Default")
      (node (ref "CN4") (pin "93") (pintype "passive"))
    )
    (net (code "388") (name "unconnected-(CN4-Pad94)") (class "Default")
      (node (ref "CN4") (pin "94") (pintype "passive"))
    )
    (net (code "389") (name "unconnected-(CN4-Pad95)") (class "Default")
      (node (ref "CN4") (pin "95") (pintype "passive"))
    )
    (net (code "390") (name "unconnected-(CN4-Pad97)") (class "Default")
      (node (ref "CN4") (pin "97") (pintype "passive"))
    )
    (net (code "391") (name "unconnected-(CN4-Pad98)") (class "Default")
      (node (ref "CN4") (pin "98") (pintype "passive"))
    )
    (net (code "392") (name "unconnected-(CN4-Pad99)") (class "Default")
      (node (ref "CN4") (pin "99") (pintype "passive"))
    )
    (net (code "393") (name "unconnected-(CN4-Pad101)") (class "Default")
      (node (ref "CN4") (pin "101") (pintype "passive"))
    )
    (net (code "394") (name "unconnected-(CN4-Pad102)") (class "Default")
      (node (ref "CN4") (pin "102") (pintype "passive"))
    )
    (net (code "395") (name "unconnected-(CN4-Pad103)") (class "Default")
      (node (ref "CN4") (pin "103") (pintype "passive"))
    )
    (net (code "396") (name "unconnected-(CN4-Pad105)") (class "Default")
      (node (ref "CN4") (pin "105") (pintype "passive"))
    )
    (net (code "397") (name "unconnected-(CN4-Pad106)") (class "Default")
      (node (ref "CN4") (pin "106") (pintype "passive"))
    )
    (net (code "398") (name "unconnected-(CN4-Pad107)") (class "Default")
      (node (ref "CN4") (pin "107") (pintype "passive"))
    )
    (net (code "399") (name "unconnected-(CN4-Pad109)") (class "Default")
      (node (ref "CN4") (pin "109") (pintype "passive"))
    )
    (net (code "400") (name "unconnected-(CN4-Pad110)") (class "Default")
      (node (ref "CN4") (pin "110") (pintype "passive"))
    )
    (net (code "401") (name "unconnected-(CN4-Pad111)") (class "Default")
      (node (ref "CN4") (pin "111") (pintype "passive"))
    )
    (net (code "402") (name "unconnected-(CN4-Pad113)") (class "Default")
      (node (ref "CN4") (pin "113") (pintype "passive"))
    )
    (net (code "403") (name "unconnected-(CN4-Pad114)") (class "Default")
      (node (ref "CN4") (pin "114") (pintype "passive"))
    )
    (net (code "404") (name "unconnected-(CN4-Pad115)") (class "Default")
      (node (ref "CN4") (pin "115") (pintype "passive"))
    )
  )
)
